# DSP_Lab_SS21_Keyboard.net
KiCad netlist of a schematic drawn in EAGLE
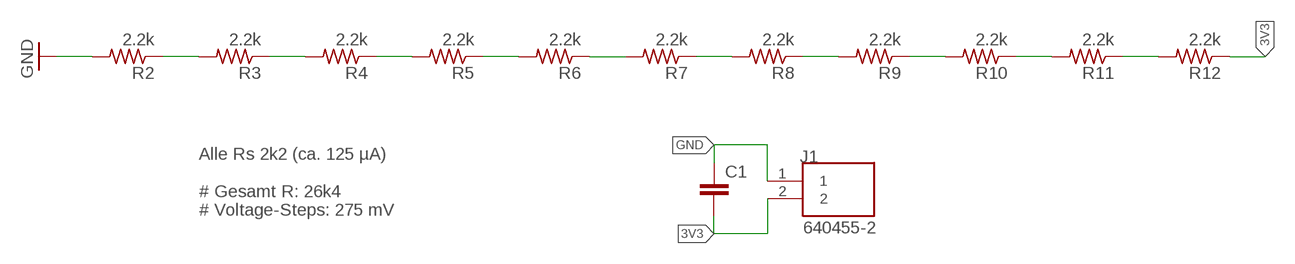
[diagram p0: schematic, sheet 1]

(export (version "E")
  (design (tool "Eeschema 10.0.6"))
  (components
    (comp (ref "C1")
      (value "C-EUC0603")
      (footprint "eagle-import:C0603")
      (libsource (lib "eagle-import") (part "C-EUC0603"))
    )
    (comp (ref "J1")
      (value "640455-2")
      (footprint "eagle-import:TE_640455-2")
      (fields (field (name "MF") "TE Connectivity"))
      (libsource (lib "eagle-import") (part "640455-2"))
    )
    (comp (ref "R2")
      (value "2.2k")
      (footprint "eagle-import:R0603")
      (libsource (lib "eagle-import") (part "R-US_R0603"))
    )
    (comp (ref "R3")
      (value "2.2k")
      (footprint "eagle-import:R0603")
      (libsource (lib "eagle-import") (part "R-US_R0603"))
    )
    (comp (ref "R4")
      (value "2.2k")
      (footprint "eagle-import:R0603")
      (libsource (lib "eagle-import") (part "R-US_R0603"))
    )
    (comp (ref "R5")
      (value "2.2k")
      (footprint "eagle-import:R0603")
      (libsource (lib "eagle-import") (part "R-US_R0603"))
    )
    (comp (ref "R6")
      (value "2.2k")
      (footprint "eagle-import:R0603")
      (libsource (lib "eagle-import") (part "R-US_R0603"))
    )
    (comp (ref "R7")
      (value "2.2k")
      (footprint "eagle-import:R0603")
      (libsource (lib "eagle-import") (part "R-US_R0603"))
    )
    (comp (ref "R8")
      (value "2.2k")
      (footprint "eagle-import:R0603")
      (libsource (lib "eagle-import") (part "R-US_R0603"))
    )
    (comp (ref "R9")
      (value "2.2k")
      (footprint "eagle-import:R0603")
      (libsource (lib "eagle-import") (part "R-US_R0603"))
    )
    (comp (ref "R10")
      (value "2.2k")
      (footprint "eagle-import:R0603")
      (libsource (lib "eagle-import") (part "R-US_R0603"))
    )
    (comp (ref "R11")
      (value "2.2k")
      (footprint "eagle-import:R0603")
      (libsource (lib "eagle-import") (part "R-US_R0603"))
    )
    (comp (ref "R12")
      (value "2.2k")
      (footprint "eagle-import:R0603")
      (libsource (lib "eagle-import") (part "R-US_R0603"))
    )
  )
  (nets
    (net (code "1") (name "3V3") (class "Default")
      (node (ref "C1") (pin "2") (pinfunction "2_2") (pintype "passive"))
      (node (ref "J1") (pin "2") (pinfunction "2_2") (pintype "passive"))
      (node (ref "R12") (pin "1") (pinfunction "1_1") (pintype "passive"))
    )
    (net (code "2") (name "GND") (class "Default")
      (node (ref "C1") (pin "1") (pinfunction "1_1") (pintype "passive"))
      (node (ref "J1") (pin "1") (pinfunction "1_1") (pintype "passive"))
      (node (ref "R2") (pin "2") (pinfunction "2_2") (pintype "passive"))
    )
    (net (code "3") (name "Net-(R2-Pad1)") (class "Default")
      (node (ref "R2") (pin "1") (pinfunction "1_1") (pintype "passive"))
      (node (ref "R3") (pin "2") (pinfunction "2_2") (pintype "passive"))
    )
    (net (code "4") (name "Net-(R3-Pad1)") (class "Default")
      (node (ref "R3") (pin "1") (pinfunction "1_1") (pintype "passive"))
      (node (ref "R4") (pin "2") (pinfunction "2_2") (pintype "passive"))
    )
    (net (code "5") (name "Net-(R4-Pad1)") (class "Default")
      (node (ref "R4") (pin "1") (pinfunction "1_1") (pintype "passive"))
      (node (ref "R5") (pin "2") (pinfunction "2_2") (pintype "passive"))
    )
    (net (code "6") (name "Net-(R5-Pad1)") (class "Default")
      (node (ref "R5") (pin "1") (pinfunction "1_1") (pintype "passive"))
      (node (ref "R6") (pin "2") (pinfunction "2_2") (pintype "passive"))
    )
    (net (code "7") (name "Net-(R6-Pad1)") (class "Default")
      (node (ref "R6") (pin "1") (pinfunction "1_1") (pintype "passive"))
      (node (ref "R7") (pin "2") (pinfunction "2_2") (pintype "passive"))
    )
    (net (code "8") (name "Net-(R7-Pad1)") (class "Default")
      (node (ref "R7") (pin "1") (pinfunction "1_1") (pintype "passive"))
      (node (ref "R8") (pin "2") (pinfunction "2_2") (pintype "passive"))
    )
    (net (code "9") (name "Net-(R8-Pad1)") (class "Default")
      (node (ref "R8") (pin "1") (pinfunction "1_1") (pintype "passive"))
      (node (ref "R9") (pin "2") (pinfunction "2_2") (pintype "passive"))
    )
    (net (code "10") (name "Net-(R10-Pad1)") (class "Default")
      (node (ref "R10") (pin "1") (pinfunction "1_1") (pintype "passive"))
      (node (ref "R11") (pin "2") (pinfunction "2_2") (pintype "passive"))
    )
    (net (code "11") (name "Net-(R10-Pad2)") (class "Default")
      (node (ref "R10") (pin "2") (pinfunction "2_2") (pintype "passive"))
      (node (ref "R9") (pin "1") (pinfunction "1_1") (pintype "passive"))
    )
    (net (code "12") (name "Net-(R11-Pad1)") (class "Default")
      (node (ref "R11") (pin "1") (pinfunction "1_1") (pintype "passive"))
      (node (ref "R12") (pin "2") (pinfunction "2_2") (pintype "passive"))
    )
  )
)
